# NRF24L01_PA.net
KiCad netlist of a schematic drawn in Altium Designer
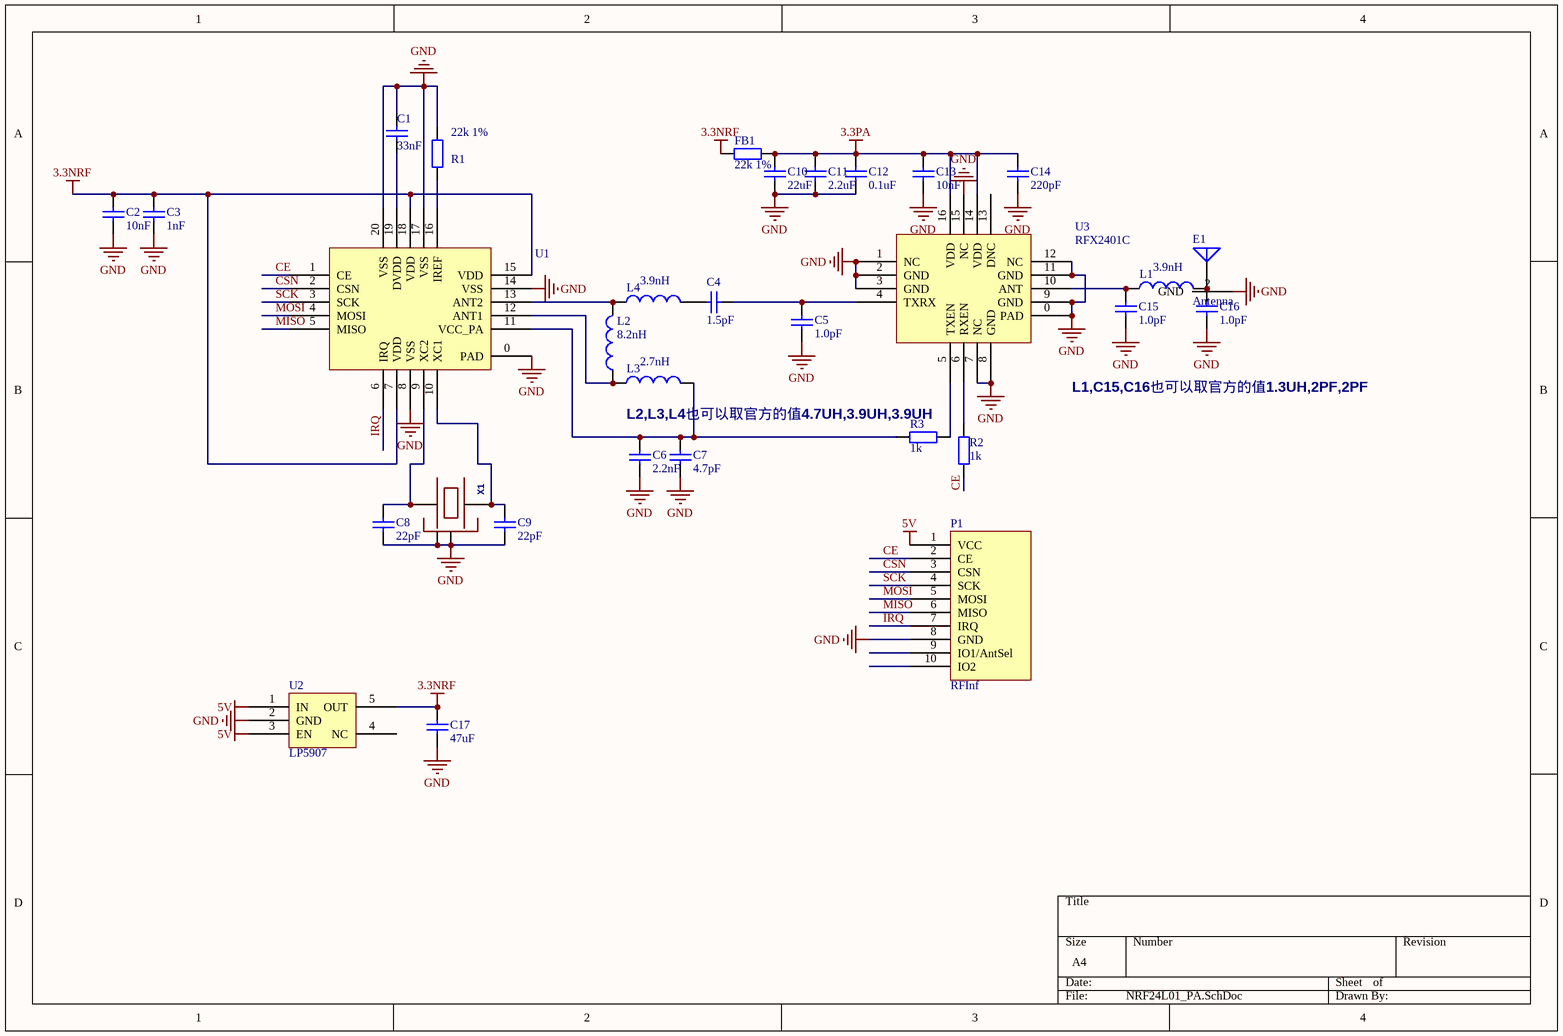
[diagram p0: NRF24L01_PA.SchDoc]

(export (version "E")
  (design (tool "Eeschema 10.0.6"))
  (components
    (comp (ref "C1")
      (value "33nF")
      (footprint "0402")
      (description "Capacitor")
      (fields (field (name "Comment") "Cap") (field (name "PUBLISHER") "Altium Limited"))
      (libsource (lib "RTC6705") (part "Cap"))
    )
    (comp (ref "C2")
      (value "10nF")
      (footprint "0402")
      (description "Capacitor")
      (fields (field (name "Comment") "Cap") (field (name "PUBLISHER") "Altium Limited"))
      (libsource (lib "RTC6705") (part "Cap"))
    )
    (comp (ref "C3")
      (value "1nF")
      (footprint "0402")
      (description "Capacitor")
      (fields (field (name "Comment") "Cap") (field (name "PUBLISHER") "Altium Limited"))
      (libsource (lib "RTC6705") (part "Cap"))
    )
    (comp (ref "C4")
      (value "1.5pF")
      (footprint "0402")
      (description "Capacitor")
      (fields (field (name "Comment") "Cap") (field (name "PUBLISHER") "Altium Limited"))
      (libsource (lib "RTC6705") (part "Cap"))
    )
    (comp (ref "C5")
      (value "1.0pF")
      (footprint "0402")
      (description "Capacitor")
      (fields (field (name "Comment") "Cap") (field (name "PUBLISHER") "Altium Limited"))
      (libsource (lib "RTC6705") (part "Cap"))
    )
    (comp (ref "C6")
      (value "2.2nF")
      (footprint "0402")
      (description "Capacitor")
      (fields (field (name "Comment") "Cap") (field (name "PUBLISHER") "Altium Limited"))
      (libsource (lib "RTC6705") (part "Cap"))
    )
    (comp (ref "C7")
      (value "4.7pF")
      (footprint "0402")
      (description "Capacitor")
      (fields (field (name "Comment") "Cap") (field (name "PUBLISHER") "Altium Limited"))
      (libsource (lib "RTC6705") (part "Cap"))
    )
    (comp (ref "C8")
      (value "22pF")
      (footprint "0402")
      (description "Capacitor")
      (fields (field (name "Comment") "Cap") (field (name "PUBLISHER") "Altium Limited"))
      (libsource (lib "RTC6705") (part "Cap"))
    )
    (comp (ref "C9")
      (value "22pF")
      (footprint "0402")
      (description "Capacitor")
      (fields (field (name "Comment") "Cap") (field (name "PUBLISHER") "Altium Limited"))
      (libsource (lib "RTC6705") (part "Cap"))
    )
    (comp (ref "C10")
      (value "22uF")
      (footprint "0805")
      (description "Capacitor")
      (fields (field (name "Comment") "Cap") (field (name "PUBLISHER") "Altium Limited"))
      (libsource (lib "RTC6705") (part "Cap"))
    )
    (comp (ref "C11")
      (value "2.2uF")
      (footprint "0402")
      (description "Capacitor")
      (fields (field (name "Comment") "Cap") (field (name "PUBLISHER") "Altium Limited"))
      (libsource (lib "RTC6705") (part "Cap"))
    )
    (comp (ref "C12")
      (value "0.1uF")
      (footprint "0402")
      (description "Capacitor")
      (fields (field (name "Comment") "Cap") (field (name "PUBLISHER") "Altium Limited"))
      (libsource (lib "RTC6705") (part "Cap"))
    )
    (comp (ref "C13")
      (value "10nF")
      (footprint "0402")
      (description "Capacitor")
      (fields (field (name "Comment") "Cap") (field (name "PUBLISHER") "Altium Limited"))
      (libsource (lib "RTC6705") (part "Cap"))
    )
    (comp (ref "C14")
      (value "220pF")
      (footprint "0402")
      (description "Capacitor")
      (fields (field (name "Comment") "Cap") (field (name "PUBLISHER") "Altium Limited"))
      (libsource (lib "RTC6705") (part "Cap"))
    )
    (comp (ref "C15")
      (value "1.0pF")
      (footprint "0402")
      (description "Capacitor")
      (fields (field (name "Comment") "Cap") (field (name "PUBLISHER") "Altium Limited"))
      (libsource (lib "RTC6705") (part "Cap"))
    )
    (comp (ref "C16")
      (value "1.0pF")
      (footprint "0402")
      (description "Capacitor")
      (fields (field (name "Comment") "Cap") (field (name "PUBLISHER") "Altium Limited"))
      (libsource (lib "RTC6705") (part "Cap"))
    )
    (comp (ref "C17")
      (value "47uF")
      (footprint "0805")
      (description "Capacitor")
      (fields (field (name "Comment") "Cap") (field (name "PUBLISHER") "Altium Limited"))
      (libsource (lib "RTC6705") (part "Cap"))
    )
    (comp (ref "E1")
      (value "Antenna")
      (footprint "IPEX")
      (description "Generic Antenna")
      (fields (field (name "PUBLISHER") "Altium Limited"))
      (libsource (lib "Miscellaneous Devices") (part "Antenna"))
    )
    (comp (ref "FB1")
      (value "22k 1%")
      (footprint "0603")
      (description "Resistor")
      (fields (field (name "Comment") "Res2") (field (name "PUBLISHER") "Altium Limited"))
      (libsource (lib "") (part "Res2_2"))
    )
    (comp (ref "L1")
      (value "3.9nH")
      (footprint "0402")
      (description "Inductor")
      (fields (field (name "PUBLISHER") "Altium Limited"))
      (libsource (lib "Miscellaneous Devices") (part "Inductor"))
    )
    (comp (ref "L2")
      (value "8.2nH")
      (footprint "0402")
      (description "Inductor")
      (fields (field (name "PUBLISHER") "Altium Limited"))
      (libsource (lib "Miscellaneous Devices") (part "Inductor"))
    )
    (comp (ref "L3")
      (value "2.7nH")
      (footprint "0402")
      (description "Inductor")
      (fields (field (name "PUBLISHER") "Altium Limited"))
      (libsource (lib "Miscellaneous Devices") (part "Inductor"))
    )
    (comp (ref "L4")
      (value "3.9nH")
      (footprint "0402")
      (description "Inductor")
      (fields (field (name "PUBLISHER") "Altium Limited"))
      (libsource (lib "Miscellaneous Devices") (part "Inductor"))
    )
    (comp (ref "P1") (value "RFInf") (footprint "RFInf") (libsource (lib "NRF24L01_PA") (part "RFInf")))
    (comp (ref "R1")
      (value "22k 1%")
      (footprint "0402")
      (description "Resistor")
      (fields (field (name "Comment") "Res2") (field (name "PUBLISHER") "Altium Limited"))
      (libsource (lib "") (part "Res2_1"))
    )
    (comp (ref "R2")
      (value "1k")
      (footprint "0402")
      (description "Resistor")
      (fields (field (name "Comment") "Res2") (field (name "PUBLISHER") "Altium Limited"))
      (libsource (lib "RTC6705") (part "Res2"))
    )
    (comp (ref "R3")
      (value "1k")
      (footprint "0402")
      (description "Resistor")
      (fields (field (name "Comment") "Res2") (field (name "PUBLISHER") "Altium Limited"))
      (libsource (lib "") (part "Res2_2"))
    )
    (comp (ref "U1")
      (value "NRF24L01")
      (footprint "NRF24L01")
      (libsource (lib "NRF24L01_PA") (part "NRF24L01"))
    )
    (comp (ref "U2") (value "LP5907") (footprint "SOT23-5") (libsource (lib "RTC6705") (part "LP5907")))
    (comp (ref "U3")
      (value "RFX2401C")
      (footprint "RFX2401C")
      (libsource (lib "NRF24L01_PA") (part "RFX2401C"))
    )
    (comp (ref "X1")
      (value "16Mhz")
      (footprint "OSCILLATOR-3.2X2.5")
      (description "Crystal Oscillator in 3.2x2.5 SMD")
      (libsource (lib "pixhawk2") (part "OSCILLATOR-3.2X2.5"))
    )
  )
  (nets
    (net (code "1") (name "/CE") (class "Default")
      (node (ref "P1") (pin "2") (pinfunction "CE_2") (pintype "passive"))
      (node (ref "R2") (pin "1") (pinfunction "1_1") (pintype "passive"))
      (node (ref "U1") (pin "1") (pinfunction "CE_1") (pintype "passive"))
    )
    (net (code "2") (name "/CSN") (class "Default")
      (node (ref "P1") (pin "3") (pinfunction "CSN_3") (pintype "passive"))
      (node (ref "U1") (pin "2") (pinfunction "CSN_2") (pintype "passive"))
    )
    (net (code "3") (name "/IRQ") (class "Default")
      (node (ref "P1") (pin "7") (pinfunction "IRQ_7") (pintype "passive"))
      (node (ref "U1") (pin "6") (pinfunction "IRQ_6") (pintype "passive"))
    )
    (net (code "4") (name "/MISO") (class "Default")
      (node (ref "P1") (pin "6") (pinfunction "MISO_6") (pintype "passive"))
      (node (ref "U1") (pin "5") (pinfunction "MISO_5") (pintype "passive"))
    )
    (net (code "5") (name "/MOSI") (class "Default")
      (node (ref "P1") (pin "5") (pinfunction "MOSI_5") (pintype "passive"))
      (node (ref "U1") (pin "4") (pinfunction "MOSI_4") (pintype "passive"))
    )
    (net (code "6") (name "/SCK") (class "Default")
      (node (ref "P1") (pin "4") (pinfunction "SCK_4") (pintype "passive"))
      (node (ref "U1") (pin "3") (pinfunction "SCK_3") (pintype "passive"))
    )
    (net (code "7") (name "3.3NRF") (class "Default")
      (node (ref "C17") (pin "1") (pinfunction "1_1") (pintype "passive"))
      (node (ref "C2") (pin "1") (pinfunction "1_1") (pintype "passive"))
      (node (ref "C3") (pin "1") (pinfunction "1_1") (pintype "passive"))
      (node (ref "FB1") (pin "1") (pinfunction "1_1") (pintype "passive"))
      (node (ref "U1") (pin "15") (pinfunction "VDD_15") (pintype "passive"))
      (node (ref "U1") (pin "18") (pinfunction "VDD_18") (pintype "passive"))
      (node (ref "U1") (pin "7") (pinfunction "VDD_7") (pintype "passive"))
      (node (ref "U2") (pin "5") (pinfunction "OUT_5") (pintype "passive"))
    )
    (net (code "8") (name "3.3PA") (class "Default")
      (node (ref "C10") (pin "1") (pinfunction "1_1") (pintype "passive"))
      (node (ref "C11") (pin "1") (pinfunction "1_1") (pintype "passive"))
      (node (ref "C12") (pin "1") (pinfunction "1_1") (pintype "passive"))
      (node (ref "C13") (pin "1") (pinfunction "1_1") (pintype "passive"))
      (node (ref "C14") (pin "1") (pinfunction "1_1") (pintype "passive"))
      (node (ref "FB1") (pin "2") (pinfunction "2_2") (pintype "passive"))
      (node (ref "U3") (pin "14") (pinfunction "VDD_14") (pintype "passive"))
      (node (ref "U3") (pin "16") (pinfunction "VDD_16") (pintype "passive"))
    )
    (net (code "9") (name "5V") (class "Default")
      (node (ref "P1") (pin "1") (pinfunction "VCC_1") (pintype "passive"))
      (node (ref "U2") (pin "1") (pinfunction "IN_1") (pintype "passive"))
      (node (ref "U2") (pin "3") (pinfunction "EN_3") (pintype "passive"))
    )
    (net (code "10") (name "GND") (class "Default")
      (node (ref "C1") (pin "1") (pinfunction "1_1") (pintype "passive"))
      (node (ref "C10") (pin "2") (pinfunction "2_2") (pintype "passive"))
      (node (ref "C11") (pin "2") (pinfunction "2_2") (pintype "passive"))
      (node (ref "C12") (pin "2") (pinfunction "2_2") (pintype "passive"))
      (node (ref "C13") (pin "2") (pinfunction "2_2") (pintype "passive"))
      (node (ref "C14") (pin "2") (pinfunction "2_2") (pintype "passive"))
      (node (ref "C15") (pin "2") (pinfunction "2_2") (pintype "passive"))
      (node (ref "C16") (pin "2") (pinfunction "2_2") (pintype "passive"))
      (node (ref "C17") (pin "2") (pinfunction "2_2") (pintype "passive"))
      (node (ref "C2") (pin "2") (pinfunction "2_2") (pintype "passive"))
      (node (ref "C3") (pin "2") (pinfunction "2_2") (pintype "passive"))
      (node (ref "C5") (pin "2") (pinfunction "2_2") (pintype "passive"))
      (node (ref "C6") (pin "2") (pinfunction "2_2") (pintype "passive"))
      (node (ref "C7") (pin "2") (pinfunction "2_2") (pintype "passive"))
      (node (ref "C8") (pin "2") (pinfunction "2_2") (pintype "passive"))
      (node (ref "C9") (pin "2") (pinfunction "2_2") (pintype "passive"))
      (node (ref "E1") (pin "2") (pinfunction "GND_2") (pintype "passive"))
      (node (ref "P1") (pin "8") (pinfunction "GND_8") (pintype "passive"))
      (node (ref "R1") (pin "1") (pinfunction "1_1") (pintype "passive"))
      (node (ref "U1") (pin "0") (pinfunction "PAD_0") (pintype "passive"))
      (node (ref "U1") (pin "14") (pinfunction "VSS_14") (pintype "passive"))
      (node (ref "U1") (pin "17") (pinfunction "VSS_17") (pintype "passive"))
      (node (ref "U1") (pin "20") (pinfunction "VSS_20") (pintype "passive"))
      (node (ref "U1") (pin "8") (pinfunction "VSS_8") (pintype "passive"))
      (node (ref "U2") (pin "2") (pinfunction "GND_2") (pintype "passive"))
      (node (ref "U3") (pin "0") (pinfunction "PAD_0") (pintype "passive"))
      (node (ref "U3") (pin "1") (pinfunction "NC_1") (pintype "passive"))
      (node (ref "U3") (pin "11") (pinfunction "GND_11") (pintype "passive"))
      (node (ref "U3") (pin "12") (pinfunction "NC_12") (pintype "passive"))
      (node (ref "U3") (pin "15") (pinfunction "NC_15") (pintype "passive"))
      (node (ref "U3") (pin "2") (pinfunction "GND_2") (pintype "passive"))
      (node (ref "U3") (pin "3") (pinfunction "GND_3") (pintype "passive"))
      (node (ref "U3") (pin "7") (pinfunction "NC_7") (pintype "passive"))
      (node (ref "U3") (pin "8") (pinfunction "GND_8") (pintype "passive"))
      (node (ref "U3") (pin "9") (pinfunction "GND_9") (pintype "passive"))
      (node (ref "X1") (pin "2") (pinfunction "NC_2_2") (pintype "open_emitter"))
      (node (ref "X1") (pin "4") (pinfunction "NC_4_4") (pintype "open_emitter"))
    )
    (net (code "11") (name "Net-(C4-Pad1)") (class "Default")
      (node (ref "C4") (pin "1") (pinfunction "1_1") (pintype "passive"))
      (node (ref "L4") (pin "2") (pinfunction "2_2") (pintype "passive"))
    )
    (net (code "12") (name "Net-(E1-ANT)") (class "Default")
      (node (ref "C16") (pin "1") (pinfunction "1_1") (pintype "passive"))
      (node (ref "E1") (pin "1") (pinfunction "ANT_1") (pintype "passive"))
      (node (ref "L1") (pin "2") (pinfunction "2_2") (pintype "passive"))
    )
    (net (code "13") (name "Net-(U1-ANT1)") (class "Default")
      (node (ref "L2") (pin "1") (pinfunction "1_1") (pintype "passive"))
      (node (ref "L3") (pin "1") (pinfunction "1_1") (pintype "passive"))
      (node (ref "U1") (pin "12") (pinfunction "ANT1_12") (pintype "passive"))
    )
    (net (code "14") (name "Net-(U1-ANT2)") (class "Default")
      (node (ref "L2") (pin "2") (pinfunction "2_2") (pintype "passive"))
      (node (ref "L4") (pin "1") (pinfunction "1_1") (pintype "passive"))
      (node (ref "U1") (pin "13") (pinfunction "ANT2_13") (pintype "passive"))
    )
    (net (code "15") (name "Net-(U1-DVDD)") (class "Default")
      (node (ref "C1") (pin "2") (pinfunction "2_2") (pintype "passive"))
      (node (ref "U1") (pin "19") (pinfunction "DVDD_19") (pintype "passive"))
    )
    (net (code "16") (name "Net-(U1-IREF)") (class "Default")
      (node (ref "R1") (pin "2") (pinfunction "2_2") (pintype "passive"))
      (node (ref "U1") (pin "16") (pinfunction "IREF_16") (pintype "passive"))
    )
    (net (code "17") (name "Net-(U1-VCC_PA)") (class "Default")
      (node (ref "C6") (pin "1") (pinfunction "1_1") (pintype "passive"))
      (node (ref "C7") (pin "1") (pinfunction "1_1") (pintype "passive"))
      (node (ref "L3") (pin "2") (pinfunction "2_2") (pintype "passive"))
      (node (ref "R3") (pin "1") (pinfunction "1_1") (pintype "passive"))
      (node (ref "U1") (pin "11") (pinfunction "VCC_PA_11") (pintype "passive"))
    )
    (net (code "18") (name "Net-(U1-XC1)") (class "Default")
      (node (ref "C9") (pin "1") (pinfunction "1_1") (pintype "passive"))
      (node (ref "U1") (pin "10") (pinfunction "XC1_10") (pintype "passive"))
      (node (ref "X1") (pin "3") (pinfunction "3_3") (pintype "passive"))
    )
    (net (code "19") (name "Net-(U1-XC2)") (class "Default")
      (node (ref "C8") (pin "1") (pinfunction "1_1") (pintype "passive"))
      (node (ref "U1") (pin "9") (pinfunction "XC2_9") (pintype "passive"))
      (node (ref "X1") (pin "1") (pinfunction "1_1") (pintype "passive"))
    )
    (net (code "20") (name "Net-(U3-ANT)") (class "Default")
      (node (ref "C15") (pin "1") (pinfunction "1_1") (pintype "passive"))
      (node (ref "L1") (pin "1") (pinfunction "1_1") (pintype "passive"))
      (node (ref "U3") (pin "10") (pinfunction "ANT_10") (pintype "passive"))
    )
    (net (code "21") (name "Net-(U3-RXEN)") (class "Default")
      (node (ref "R2") (pin "2") (pinfunction "2_2") (pintype "passive"))
      (node (ref "U3") (pin "6") (pinfunction "RXEN_6") (pintype "passive"))
    )
    (net (code "22") (name "Net-(U3-TXEN)") (class "Default")
      (node (ref "R3") (pin "2") (pinfunction "2_2") (pintype "passive"))
      (node (ref "U3") (pin "5") (pinfunction "TXEN_5") (pintype "passive"))
    )
    (net (code "23") (name "Net-(U3-TXRX)") (class "Default")
      (node (ref "C4") (pin "2") (pinfunction "2_2") (pintype "passive"))
      (node (ref "C5") (pin "1") (pinfunction "1_1") (pintype "passive"))
      (node (ref "U3") (pin "4") (pinfunction "TXRX_4") (pintype "passive"))
    )
    (net (code "24") (name "unconnected-(P1-IO1{slash}AntSel-Pad9)") (class "Default")
      (node (ref "P1") (pin "9") (pinfunction "IO1/AntSel_9") (pintype "passive"))
    )
    (net (code "25") (name "unconnected-(P1-IO2-Pad10)") (class "Default")
      (node (ref "P1") (pin "10") (pinfunction "IO2_10") (pintype "passive"))
    )
    (net (code "26") (name "unconnected-(U2-NC-Pad4)") (class "Default")
      (node (ref "U2") (pin "4") (pinfunction "NC_4") (pintype "passive"))
    )
    (net (code "27") (name "unconnected-(U3-DNC-Pad13)") (class "Default")
      (node (ref "U3") (pin "13") (pinfunction "DNC_13") (pintype "passive"))
    )
  )
)
